# maple-base.net
KiCad netlist of a schematic drawn in EAGLE
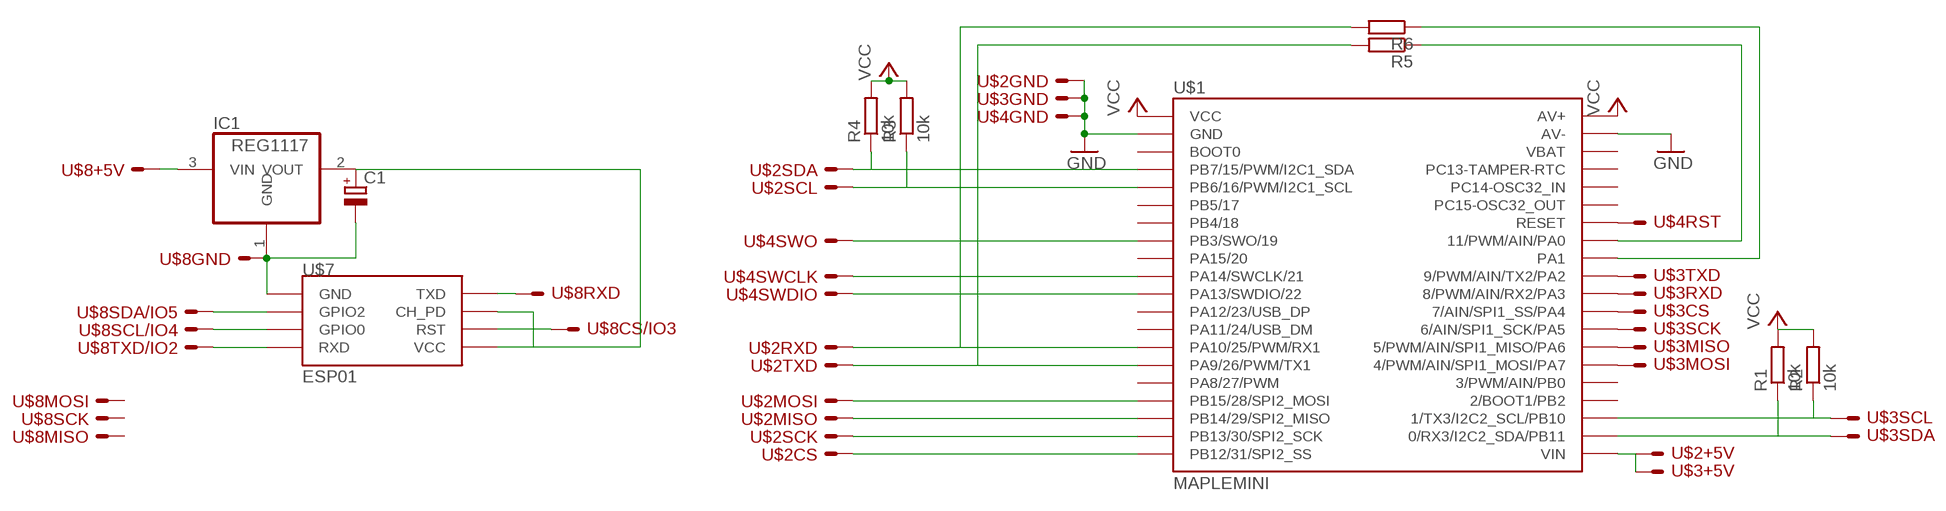
[diagram p0: schematic, sheet 1]

(export (version "E")
  (design (tool "Eeschema 10.0.6"))
  (components
    (comp (ref "C1")
      (value "CPOL-EUB45181A")
      (footprint "eagle-import:B45181A")
      (libsource (lib "eagle-import") (part "CPOL-EUB45181A"))
    )
    (comp (ref "IC1")
      (value "REG1117")
      (footprint "eagle-import:SOT223")
      (libsource (lib "eagle-import") (part "REG1117"))
    )
    (comp (ref "R1")
      (value "10k")
      (footprint "eagle-import:0207_7")
      (libsource (lib "eagle-import") (part "R-EU_0207/7"))
    )
    (comp (ref "R2")
      (value "10k")
      (footprint "eagle-import:0207_7")
      (libsource (lib "eagle-import") (part "R-EU_0207/7"))
    )
    (comp (ref "R3")
      (value "10k")
      (footprint "eagle-import:0207_7")
      (libsource (lib "eagle-import") (part "R-EU_0207/7"))
    )
    (comp (ref "R4")
      (value "10k")
      (footprint "eagle-import:0207_7")
      (libsource (lib "eagle-import") (part "R-EU_0207/7"))
    )
    (comp (ref "R5")
      (value "R-EU_0207/7")
      (footprint "eagle-import:0207_7")
      (libsource (lib "eagle-import") (part "R-EU_0207/7"))
    )
    (comp (ref "R6")
      (value "R-EU_0207/7")
      (footprint "eagle-import:0207_7")
      (libsource (lib "eagle-import") (part "R-EU_0207/7"))
    )
    (comp (ref "U$1")
      (value "MAPLEMINI")
      (footprint "eagle-import:20-DIP")
      (libsource (lib "eagle-import") (part "MAPLEMINI"))
    )
    (comp (ref "U$2")
      (value "SPI_BUS")
      (footprint "eagle-import:SPI_BUS")
      (libsource (lib "eagle-import") (part "SPI_BUS"))
    )
    (comp (ref "U$3")
      (value "SPI_BUS")
      (footprint "eagle-import:SPI_BUS")
      (libsource (lib "eagle-import") (part "SPI_BUS"))
    )
    (comp (ref "U$4")
      (value "SWD")
      (footprint "eagle-import:SWD")
      (libsource (lib "eagle-import") (part "SWD"))
    )
    (comp (ref "U$7")
      (value "ESP01")
      (footprint "eagle-import:ESP01")
      (libsource (lib "eagle-import") (part "ESP01"))
    )
    (comp (ref "U$8")
      (value "LIMERO_BUS")
      (footprint "eagle-import:SPI_BUS")
      (libsource (lib "eagle-import") (part "LIMERO_BUS"))
    )
  )
  (nets
    (net (code "1") (name "GND") (class "Default")
      (node (ref "U$1") (pin "2") (pinfunction "GND_2") (pintype "bidirectional"))
      (node (ref "U$1") (pin "39") (pinfunction "AV-_39") (pintype "bidirectional"))
      (node (ref "U$2") (pin "GND") (pinfunction "S_GND") (pintype "passive"))
      (node (ref "U$3") (pin "GND") (pinfunction "S_GND") (pintype "passive"))
      (node (ref "U$4") (pin "GND") (pinfunction "S_GND") (pintype "passive"))
    )
    (net (code "2") (name "Net-(IC1-GND)") (class "Default")
      (node (ref "C1") (pin "-") (pinfunction "-_-") (pintype "passive"))
      (node (ref "IC1") (pin "1") (pinfunction "GND_1") (pintype "power_in"))
      (node (ref "U$7") (pin "GND") (pinfunction "GND_GND") (pintype "bidirectional"))
      (node (ref "U$8") (pin "GND") (pinfunction "S_GND") (pintype "passive"))
    )
    (net (code "3") (name "Net-(IC1-VIN)") (class "Default")
      (node (ref "IC1") (pin "3") (pinfunction "VIN_3") (pintype "input"))
      (node (ref "U$8") (pin "+5V") (pinfunction "S_+5V") (pintype "passive"))
    )
    (net (code "4") (name "Net-(IC1-VOUT)") (class "Default")
      (node (ref "C1") (pin "+") (pinfunction "+_+") (pintype "passive"))
      (node (ref "IC1") (pin "2") (pinfunction "VOUT_2") (pintype "output"))
      (node (ref "U$7") (pin "CH_PD") (pinfunction "CH_PD_CH_PD") (pintype "bidirectional"))
      (node (ref "U$7") (pin "VCC") (pinfunction "VCC_VCC") (pintype "bidirectional"))
    )
    (net (code "5") (name "Net-(U$1-0{slash}RX3{slash}I2C2_SDA{slash}PB11)") (class "Default")
      (node (ref "R1") (pin "1") (pinfunction "1_1") (pintype "passive"))
      (node (ref "U$1") (pin "22") (pinfunction "0/RX3/I2C2_SDA/PB11_22") (pintype "bidirectional"))
      (node (ref "U$3") (pin "SDA") (pinfunction "S_SDA") (pintype "passive"))
    )
    (net (code "6") (name "Net-(U$1-1{slash}TX3{slash}I2C2_SCL{slash}PB10)") (class "Default")
      (node (ref "R2") (pin "1") (pinfunction "1_1") (pintype "passive"))
      (node (ref "U$1") (pin "23") (pinfunction "1/TX3/I2C2_SCL/PB10_23") (pintype "bidirectional"))
      (node (ref "U$3") (pin "SCL") (pinfunction "S_SCL") (pintype "passive"))
    )
    (net (code "7") (name "Net-(U$1-4{slash}PWM{slash}AIN{slash}SPI1_MOSI{slash}PA7)") (class "Default")
      (node (ref "U$1") (pin "26") (pinfunction "4/PWM/AIN/SPI1_MOSI/PA7_26") (pintype "bidirectional"))
      (node (ref "U$3") (pin "MOSI") (pinfunction "S_MOSI") (pintype "passive"))
    )
    (net (code "8") (name "Net-(U$1-5{slash}PWM{slash}AIN{slash}SPI1_MISO{slash}PA6)") (class "Default")
      (node (ref "U$1") (pin "27") (pinfunction "5/PWM/AIN/SPI1_MISO/PA6_27") (pintype "bidirectional"))
      (node (ref "U$3") (pin "MISO") (pinfunction "S_MISO") (pintype "passive"))
    )
    (net (code "9") (name "Net-(U$1-6{slash}AIN{slash}SPI1_SCK{slash}PA5)") (class "Default")
      (node (ref "U$1") (pin "28") (pinfunction "6/AIN/SPI1_SCK/PA5_28") (pintype "bidirectional"))
      (node (ref "U$3") (pin "SCK") (pinfunction "S_SCK") (pintype "passive"))
    )
    (net (code "10") (name "Net-(U$1-7{slash}AIN{slash}SPI1_SS{slash}PA4)") (class "Default")
      (node (ref "U$1") (pin "29") (pinfunction "7/AIN/SPI1_SS/PA4_29") (pintype "bidirectional"))
      (node (ref "U$3") (pin "CS") (pinfunction "S_CS") (pintype "passive"))
    )
    (net (code "11") (name "Net-(U$1-8{slash}PWM{slash}AIN{slash}RX2{slash}PA3)") (class "Default")
      (node (ref "U$1") (pin "30") (pinfunction "8/PWM/AIN/RX2/PA3_30") (pintype "bidirectional"))
      (node (ref "U$3") (pin "RXD") (pinfunction "S_RXD") (pintype "passive"))
    )
    (net (code "12") (name "Net-(U$1-9{slash}PWM{slash}AIN{slash}TX2{slash}PA2)") (class "Default")
      (node (ref "U$1") (pin "31") (pinfunction "9/PWM/AIN/TX2/PA2_31") (pintype "bidirectional"))
      (node (ref "U$3") (pin "TXD") (pinfunction "S_TXD") (pintype "passive"))
    )
    (net (code "13") (name "Net-(U$1-11{slash}PWM{slash}AIN{slash}PA0)") (class "Default")
      (node (ref "R5") (pin "1") (pinfunction "1_1") (pintype "passive"))
      (node (ref "U$1") (pin "33") (pinfunction "11/PWM/AIN/PA0_33") (pintype "bidirectional"))
    )
    (net (code "14") (name "Net-(U$1-PA1)") (class "Default")
      (node (ref "R6") (pin "1") (pinfunction "1_1") (pintype "passive"))
      (node (ref "U$1") (pin "32") (pinfunction "PA1_32") (pintype "bidirectional"))
    )
    (net (code "15") (name "Net-(U$1-PA9{slash}26{slash}PWM{slash}TX1)") (class "Default")
      (node (ref "R5") (pin "2") (pinfunction "2_2") (pintype "passive"))
      (node (ref "U$1") (pin "15") (pinfunction "PA9/26/PWM/TX1_15") (pintype "bidirectional"))
      (node (ref "U$2") (pin "TXD") (pinfunction "S_TXD") (pintype "passive"))
    )
    (net (code "16") (name "Net-(U$1-PA10{slash}25{slash}PWM{slash}RX1)") (class "Default")
      (node (ref "R6") (pin "2") (pinfunction "2_2") (pintype "passive"))
      (node (ref "U$1") (pin "14") (pinfunction "PA10/25/PWM/RX1_14") (pintype "bidirectional"))
      (node (ref "U$2") (pin "RXD") (pinfunction "S_RXD") (pintype "passive"))
    )
    (net (code "17") (name "Net-(U$1-PA13{slash}SWDIO{slash}22)") (class "Default")
      (node (ref "U$1") (pin "11") (pinfunction "PA13/SWDIO/22_11") (pintype "bidirectional"))
      (node (ref "U$4") (pin "SWDIO") (pinfunction "S_SWDIO") (pintype "passive"))
    )
    (net (code "18") (name "Net-(U$1-PA14{slash}SWCLK{slash}21)") (class "Default")
      (node (ref "U$1") (pin "10") (pinfunction "PA14/SWCLK/21_10") (pintype "bidirectional"))
      (node (ref "U$4") (pin "SWCLK") (pinfunction "S_SWCLK") (pintype "passive"))
    )
    (net (code "19") (name "Net-(U$1-PB3{slash}SWO{slash}19)") (class "Default")
      (node (ref "U$1") (pin "8") (pinfunction "PB3/SWO/19_8") (pintype "bidirectional"))
      (node (ref "U$4") (pin "SWO") (pinfunction "S_SWO") (pintype "passive"))
    )
    (net (code "20") (name "Net-(U$1-PB6{slash}16{slash}PWM{slash}I2C1_SCL)") (class "Default")
      (node (ref "R3") (pin "1") (pinfunction "1_1") (pintype "passive"))
      (node (ref "U$1") (pin "5") (pinfunction "PB6/16/PWM/I2C1_SCL_5") (pintype "bidirectional"))
      (node (ref "U$2") (pin "SCL") (pinfunction "S_SCL") (pintype "passive"))
    )
    (net (code "21") (name "Net-(U$1-PB7{slash}15{slash}PWM{slash}I2C1_SDA)") (class "Default")
      (node (ref "R4") (pin "1") (pinfunction "1_1") (pintype "passive"))
      (node (ref "U$1") (pin "4") (pinfunction "PB7/15/PWM/I2C1_SDA_4") (pintype "bidirectional"))
      (node (ref "U$2") (pin "SDA") (pinfunction "S_SDA") (pintype "passive"))
    )
    (net (code "22") (name "Net-(U$1-PB12{slash}31{slash}SPI2_SS)") (class "Default")
      (node (ref "U$1") (pin "20") (pinfunction "PB12/31/SPI2_SS_20") (pintype "bidirectional"))
      (node (ref "U$2") (pin "CS") (pinfunction "S_CS") (pintype "passive"))
    )
    (net (code "23") (name "Net-(U$1-PB13{slash}30{slash}SPI2_SCK)") (class "Default")
      (node (ref "U$1") (pin "19") (pinfunction "PB13/30/SPI2_SCK_19") (pintype "bidirectional"))
      (node (ref "U$2") (pin "SCK") (pinfunction "S_SCK") (pintype "passive"))
    )
    (net (code "24") (name "Net-(U$1-PB14{slash}29{slash}SPI2_MISO)") (class "Default")
      (node (ref "U$1") (pin "18") (pinfunction "PB14/29/SPI2_MISO_18") (pintype "bidirectional"))
      (node (ref "U$2") (pin "MISO") (pinfunction "S_MISO") (pintype "passive"))
    )
    (net (code "25") (name "Net-(U$1-PB15{slash}28{slash}SPI2_MOSI)") (class "Default")
      (node (ref "U$1") (pin "17") (pinfunction "PB15/28/SPI2_MOSI_17") (pintype "bidirectional"))
      (node (ref "U$2") (pin "MOSI") (pinfunction "S_MOSI") (pintype "passive"))
    )
    (net (code "26") (name "Net-(U$1-RESET)") (class "Default")
      (node (ref "U$1") (pin "34") (pinfunction "RESET_34") (pintype "bidirectional"))
      (node (ref "U$4") (pin "RST") (pinfunction "S_RST") (pintype "passive"))
    )
    (net (code "27") (name "Net-(U$1-VIN)") (class "Default")
      (node (ref "U$1") (pin "21") (pinfunction "VIN_21") (pintype "bidirectional"))
      (node (ref "U$2") (pin "+5V") (pinfunction "S_+5V") (pintype "passive"))
      (node (ref "U$3") (pin "+5V") (pinfunction "S_+5V") (pintype "passive"))
    )
    (net (code "28") (name "Net-(U$7-RXD)") (class "Default")
      (node (ref "U$7") (pin "RX") (pinfunction "RXD_RX") (pintype "bidirectional"))
      (node (ref "U$8") (pin "TXD") (pinfunction "S_TXD") (pintype "passive"))
    )
    (net (code "29") (name "Net-(U$7-TXD)") (class "Default")
      (node (ref "U$7") (pin "TX") (pinfunction "TXD_TX") (pintype "bidirectional"))
      (node (ref "U$8") (pin "RXD") (pinfunction "S_RXD") (pintype "passive"))
    )
    (net (code "30") (name "Net-(U$8B-S)") (class "Default")
      (node (ref "U$7") (pin "RST") (pinfunction "RST_RST") (pintype "bidirectional"))
      (node (ref "U$8") (pin "CS") (pinfunction "S_CS") (pintype "passive"))
    )
    (net (code "31") (name "Net-(U$8H-S)") (class "Default")
      (node (ref "U$7") (pin "GPIO0") (pinfunction "GPIO0_GPIO0") (pintype "bidirectional"))
      (node (ref "U$8") (pin "SCL") (pinfunction "S_SCL") (pintype "passive"))
    )
    (net (code "32") (name "Net-(U$8I-S)") (class "Default")
      (node (ref "U$7") (pin "GPIO2") (pinfunction "GPIO2_GPIO2") (pintype "bidirectional"))
      (node (ref "U$8") (pin "SDA") (pinfunction "S_SDA") (pintype "passive"))
    )
    (net (code "33") (name "VCC") (class "Default")
      (node (ref "R1") (pin "2") (pinfunction "2_2") (pintype "passive"))
      (node (ref "R2") (pin "2") (pinfunction "2_2") (pintype "passive"))
      (node (ref "R3") (pin "2") (pinfunction "2_2") (pintype "passive"))
      (node (ref "R4") (pin "2") (pinfunction "2_2") (pintype "passive"))
      (node (ref "U$1") (pin "1") (pinfunction "VCC_1") (pintype "bidirectional"))
      (node (ref "U$1") (pin "40") (pinfunction "AV+_40") (pintype "bidirectional"))
    )
    (net (code "34") (name "unconnected-(U$1-2{slash}BOOT1{slash}PB2-Pad24)") (class "Default")
      (node (ref "U$1") (pin "24") (pinfunction "2/BOOT1/PB2_24") (pintype "bidirectional"))
    )
    (net (code "35") (name "unconnected-(U$1-3{slash}PWM{slash}AIN{slash}PB0-Pad25)") (class "Default")
      (node (ref "U$1") (pin "25") (pinfunction "3/PWM/AIN/PB0_25") (pintype "bidirectional"))
    )
    (net (code "36") (name "unconnected-(U$1-BOOT0-Pad3)") (class "Default")
      (node (ref "U$1") (pin "3") (pinfunction "BOOT0_3") (pintype "bidirectional"))
    )
    (net (code "37") (name "unconnected-(U$1-PA8{slash}27{slash}PWM-Pad16)") (class "Default")
      (node (ref "U$1") (pin "16") (pinfunction "PA8/27/PWM_16") (pintype "bidirectional"))
    )
    (net (code "38") (name "unconnected-(U$1-PA11{slash}24{slash}USB_DM-Pad13)") (class "Default")
      (node (ref "U$1") (pin "13") (pinfunction "PA11/24/USB_DM_13") (pintype "bidirectional"))
    )
    (net (code "39") (name "unconnected-(U$1-PA12{slash}23{slash}USB_DP-Pad12)") (class "Default")
      (node (ref "U$1") (pin "12") (pinfunction "PA12/23/USB_DP_12") (pintype "bidirectional"))
    )
    (net (code "40") (name "unconnected-(U$1-PA15{slash}20-Pad9)") (class "Default")
      (node (ref "U$1") (pin "9") (pinfunction "PA15/20_9") (pintype "bidirectional"))
    )
    (net (code "41") (name "unconnected-(U$1-PB4{slash}18-Pad7)") (class "Default")
      (node (ref "U$1") (pin "7") (pinfunction "PB4/18_7") (pintype "bidirectional"))
    )
    (net (code "42") (name "unconnected-(U$1-PB5{slash}17-Pad6)") (class "Default")
      (node (ref "U$1") (pin "6") (pinfunction "PB5/17_6") (pintype "bidirectional"))
    )
    (net (code "43") (name "unconnected-(U$1-PC13-TAMPER-RTC-Pad37)") (class "Default")
      (node (ref "U$1") (pin "37") (pinfunction "PC13-TAMPER-RTC_37") (pintype "bidirectional"))
    )
    (net (code "44") (name "unconnected-(U$1-PC14-OSC32_IN-Pad36)") (class "Default")
      (node (ref "U$1") (pin "36") (pinfunction "PC14-OSC32_IN_36") (pintype "bidirectional"))
    )
    (net (code "45") (name "unconnected-(U$1-PC15-OSC32_OUT-Pad35)") (class "Default")
      (node (ref "U$1") (pin "35") (pinfunction "PC15-OSC32_OUT_35") (pintype "bidirectional"))
    )
    (net (code "46") (name "unconnected-(U$1-VBAT-Pad38)") (class "Default")
      (node (ref "U$1") (pin "38") (pinfunction "VBAT_38") (pintype "bidirectional"))
    )
    (net (code "47") (name "unconnected-(U$8D-S-PadMISO)") (class "Default")
      (node (ref "U$8") (pin "MISO") (pinfunction "S_MISO") (pintype "passive"))
    )
    (net (code "48") (name "unconnected-(U$8E-S-PadMOSI)") (class "Default")
      (node (ref "U$8") (pin "MOSI") (pinfunction "S_MOSI") (pintype "passive"))
    )
    (net (code "49") (name "unconnected-(U$8G-S-PadSCK)") (class "Default")
      (node (ref "U$8") (pin "SCK") (pinfunction "S_SCK") (pintype "passive"))
    )
  )
)
